# sx-wdec84-1_1.net
KiCad netlist of a schematic drawn in EAGLE
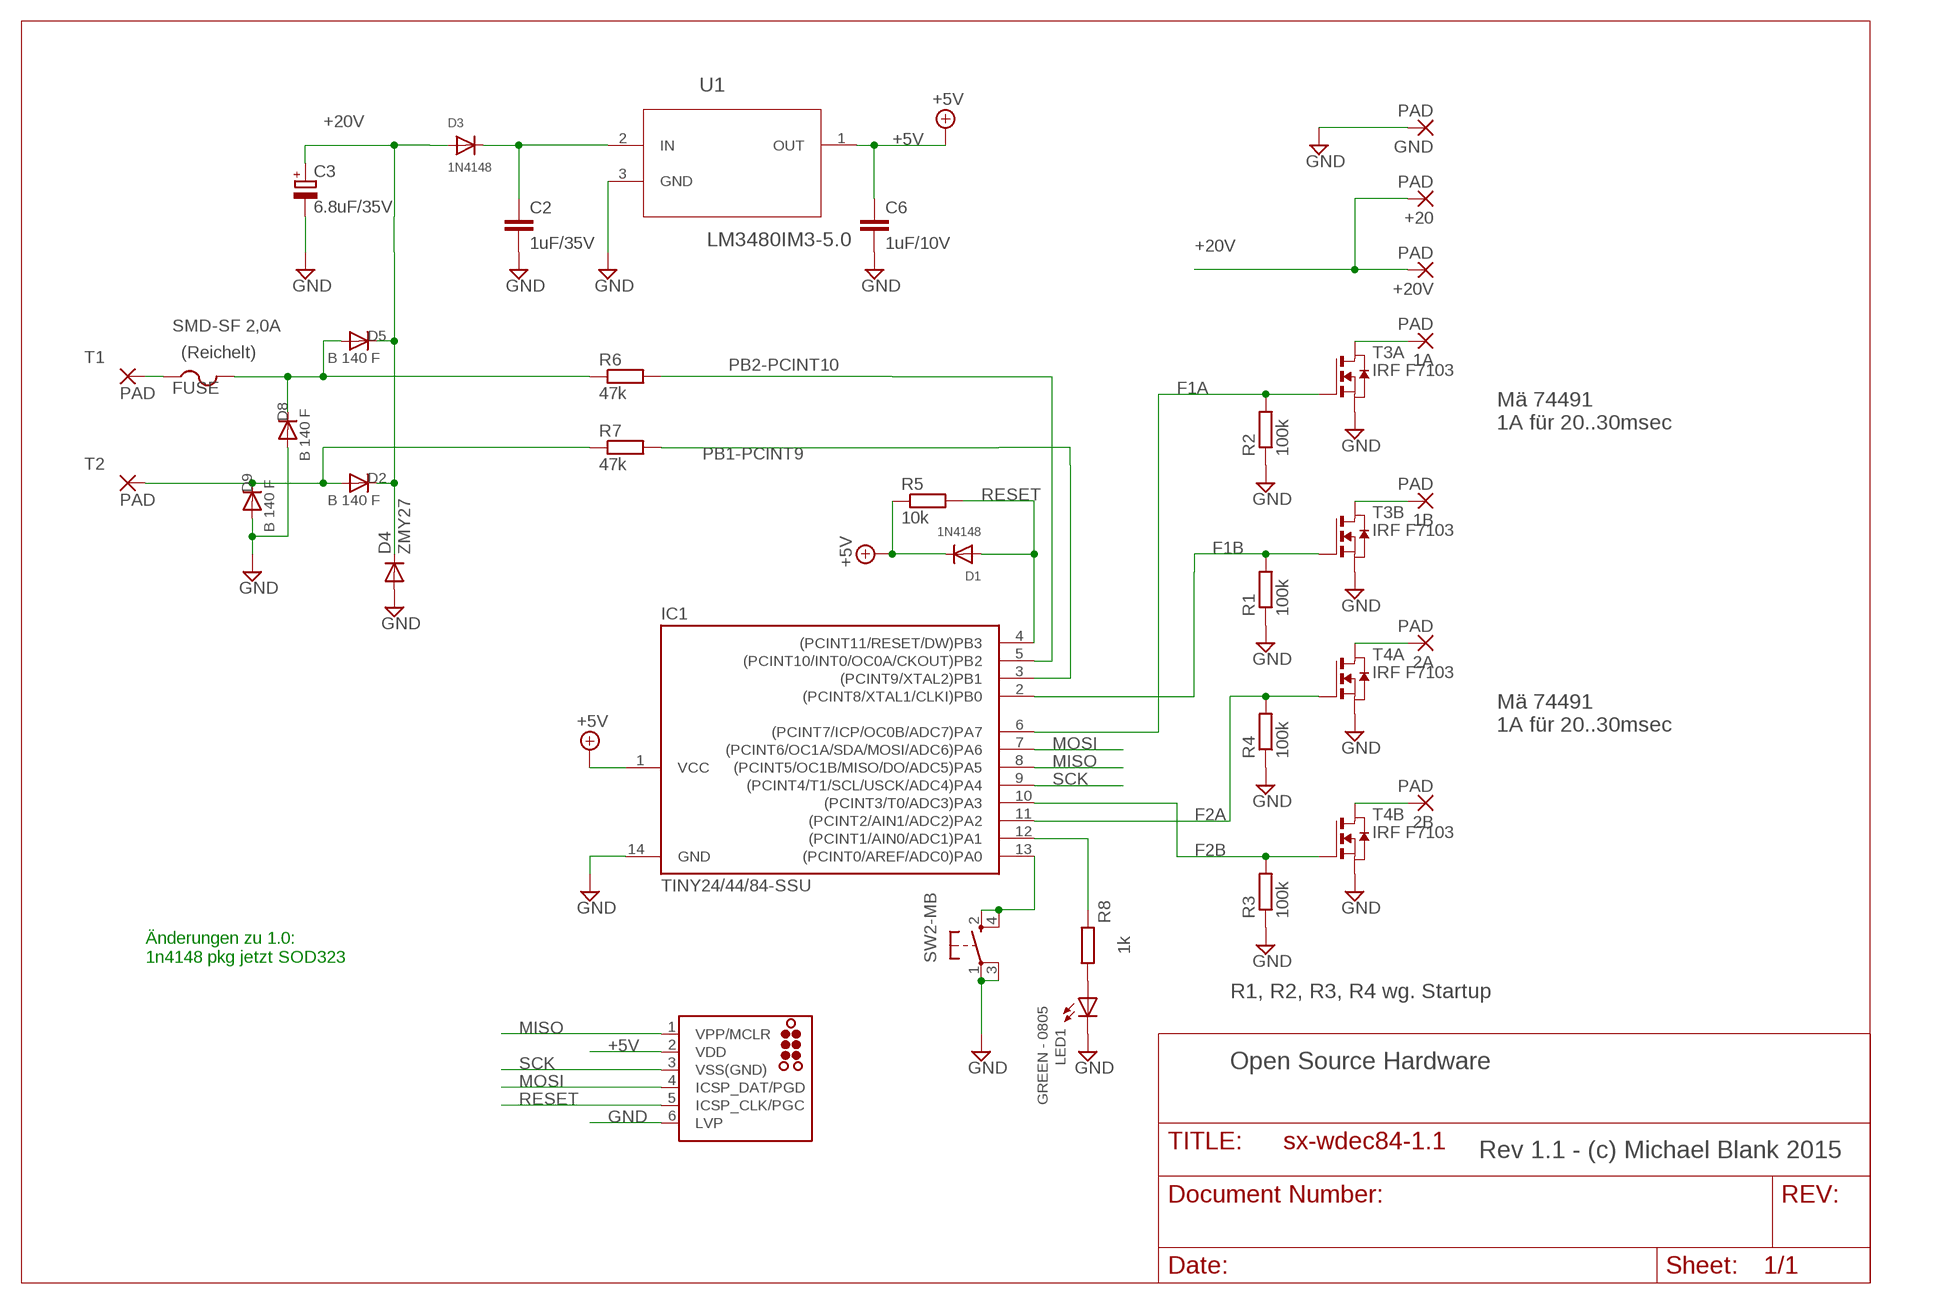
[diagram p0: schematic, sheet 1]

(export (version "E")
  (design (tool "Eeschema 10.0.6"))
  (components
    (comp (ref "+20")
      (value "PAD")
      (footprint "eagle-import:SMD1,27-2,54")
      (libsource (lib "eagle-import") (part "SMD2"))
    )
    (comp (ref "+20V")
      (value "PAD")
      (footprint "eagle-import:SMD1,27-2,54")
      (libsource (lib "eagle-import") (part "SMD2"))
    )
    (comp (ref "1A")
      (value "PAD")
      (footprint "eagle-import:SMD1,27-2,54")
      (libsource (lib "eagle-import") (part "SMD2"))
    )
    (comp (ref "1B")
      (value "PAD")
      (footprint "eagle-import:SMD1,27-2,54")
      (libsource (lib "eagle-import") (part "SMD2"))
    )
    (comp (ref "2A")
      (value "PAD")
      (footprint "eagle-import:SMD1,27-2,54")
      (libsource (lib "eagle-import") (part "SMD2"))
    )
    (comp (ref "2B")
      (value "PAD")
      (footprint "eagle-import:SMD1,27-2,54")
      (libsource (lib "eagle-import") (part "SMD2"))
    )
    (comp (ref "C2")
      (value "1uF/35V")
      (footprint "eagle-import:C0805")
      (libsource (lib "eagle-import") (part "C-EUC0805"))
    )
    (comp (ref "C3")
      (value "6.8uF/35V")
      (footprint "eagle-import:SMC_D")
      (libsource (lib "eagle-import") (part "CPOL-EUSMCD"))
    )
    (comp (ref "C6")
      (value "1uF/10V")
      (footprint "eagle-import:C0805")
      (libsource (lib "eagle-import") (part "C-EUC0805"))
    )
    (comp (ref "D1")
      (value "1N4148")
      (footprint "eagle-import:SOD-323F")
      (libsource (lib "eagle-import") (part "DIODESOD-323F"))
    )
    (comp (ref "D2")
      (value "B 140 F")
      (footprint "eagle-import:SMA-403D")
      (libsource (lib "eagle-import") (part "DIODESMA-403D"))
    )
    (comp (ref "D3")
      (value "1N4148")
      (footprint "eagle-import:SOD-323F")
      (libsource (lib "eagle-import") (part "DIODESOD-323F"))
    )
    (comp (ref "D4")
      (value "ZMY27")
      (footprint "eagle-import:MELF-MLL41")
      (libsource (lib "eagle-import") (part "DIODE-MELF-MLL41"))
    )
    (comp (ref "D5")
      (value "B 140 F")
      (footprint "eagle-import:SMA-403D")
      (libsource (lib "eagle-import") (part "DIODESMA-403D"))
    )
    (comp (ref "D8")
      (value "B 140 F")
      (footprint "eagle-import:SMA-403D")
      (libsource (lib "eagle-import") (part "DIODESMA-403D"))
    )
    (comp (ref "D9")
      (value "B 140 F")
      (footprint "eagle-import:SMA-403D")
      (libsource (lib "eagle-import") (part "DIODESMA-403D"))
    )
    (comp (ref "FUSE")
      (value "SMD-SF 2,0A")
      (footprint "eagle-import:1812")
      (libsource (lib "eagle-import") (part "PTCFUSE-1812"))
    )
    (comp (ref "GND")
      (value "PAD")
      (footprint "eagle-import:SMD1,27-2,54")
      (libsource (lib "eagle-import") (part "SMD2"))
    )
    (comp (ref "IC1")
      (value "TINY24/44/84-SSU")
      (footprint "eagle-import:SOIC14")
      (libsource (lib "eagle-import") (part "TINY24/44/84-SSU"))
    )
    (comp (ref "J1")
      (value "ISP")
      (footprint "eagle-import:TC2030-MCP-NL")
      (libsource (lib "eagle-import") (part "TC2030-MCP-NL"))
    )
    (comp (ref "LED1")
      (value "GREEN - 0805")
      (footprint "eagle-import:LED-0805")
      (libsource (lib "eagle-import") (part "LED0805"))
    )
    (comp (ref "R1")
      (value "100k")
      (footprint "eagle-import:R0805W")
      (libsource (lib "eagle-import") (part "R-EU_R0805W"))
    )
    (comp (ref "R2")
      (value "100k")
      (footprint "eagle-import:R0805W")
      (libsource (lib "eagle-import") (part "R-EU_R0805W"))
    )
    (comp (ref "R3")
      (value "100k")
      (footprint "eagle-import:R0805W")
      (libsource (lib "eagle-import") (part "R-EU_R0805W"))
    )
    (comp (ref "R4")
      (value "100k")
      (footprint "eagle-import:R0805W")
      (libsource (lib "eagle-import") (part "R-EU_R0805W"))
    )
    (comp (ref "R5")
      (value "10k")
      (footprint "eagle-import:R0805W")
      (libsource (lib "eagle-import") (part "R-EU_R0805W"))
    )
    (comp (ref "R6")
      (value "47k")
      (footprint "eagle-import:R0805W")
      (libsource (lib "eagle-import") (part "R-EU_R0805W"))
    )
    (comp (ref "R7")
      (value "47k")
      (footprint "eagle-import:R0805W")
      (libsource (lib "eagle-import") (part "R-EU_R0805W"))
    )
    (comp (ref "R8")
      (value "1k")
      (footprint "eagle-import:R0805W")
      (libsource (lib "eagle-import") (part "R-EU_R0805W"))
    )
    (comp (ref "SW2-MB")
      (value "SPST_TACT-KMR2")
      (footprint "eagle-import:KMR2")
      (libsource (lib "eagle-import") (part "SPST_TACT-KMR2"))
    )
    (comp (ref "T1")
      (value "PAD")
      (footprint "eagle-import:SMD1,27-2,54")
      (libsource (lib "eagle-import") (part "SMD2"))
    )
    (comp (ref "T2")
      (value "PAD")
      (footprint "eagle-import:SMD1,27-2,54")
      (libsource (lib "eagle-import") (part "SMD2"))
    )
    (comp (ref "T3")
      (value "IRF F7103")
      (footprint "eagle-import:SO8")
      (libsource (lib "eagle-import") (part "DMN3024LSD"))
    )
    (comp (ref "T4")
      (value "IRF F7103")
      (footprint "eagle-import:SO8")
      (libsource (lib "eagle-import") (part "DMN3024LSD"))
    )
    (comp (ref "U1")
      (value "LM3480IM3-5.0")
      (footprint "eagle-import:SOT95P263X110-3N")
      (fields (field (name "MPN") "LM3480IM3-50"))
      (libsource (lib "eagle-import") (part "LM3480IM3-5.0"))
    )
  )
  (nets
    (net (code "1") (name "+5V") (class "Default")
      (node (ref "C6") (pin "1") (pinfunction "1_1") (pintype "passive"))
      (node (ref "D1") (pin "C") (pinfunction "C_C") (pintype "passive"))
      (node (ref "IC1") (pin "1") (pinfunction "VCC_1") (pintype "power_in"))
      (node (ref "J1") (pin "2") (pinfunction "VDD_2") (pintype "power_in"))
      (node (ref "R5") (pin "1") (pinfunction "1_1") (pintype "passive"))
      (node (ref "U1") (pin "1") (pinfunction "OUT_1") (pintype "output"))
    )
    (net (code "2") (name "/+20V") (class "Default")
      (node (ref "+20") (pin "1") (pinfunction "P_1") (pintype "passive"))
      (node (ref "+20V") (pin "1") (pinfunction "P_1") (pintype "passive"))
      (node (ref "C3") (pin "+") (pinfunction "+_+") (pintype "passive"))
      (node (ref "D2") (pin "C") (pinfunction "C_C") (pintype "passive"))
      (node (ref "D3") (pin "A") (pinfunction "A_A") (pintype "passive"))
      (node (ref "D4") (pin "C") (pinfunction "C_C") (pintype "passive"))
      (node (ref "D5") (pin "C") (pinfunction "C_C") (pintype "passive"))
    )
    (net (code "3") (name "/F1A") (class "Default")
      (node (ref "IC1") (pin "6") (pinfunction "(PCINT7/ICP/OC0B/ADC7)PA7_6") (pintype "bidirectional"))
      (node (ref "R2") (pin "2") (pinfunction "2_2") (pintype "passive"))
      (node (ref "T3") (pin "2") (pinfunction "G_2") (pintype "passive"))
    )
    (net (code "4") (name "/F1B") (class "Default")
      (node (ref "IC1") (pin "2") (pinfunction "(PCINT8/XTAL1/CLKI)PB0_2") (pintype "bidirectional"))
      (node (ref "R1") (pin "2") (pinfunction "2_2") (pintype "passive"))
      (node (ref "T3") (pin "4") (pinfunction "G_4") (pintype "passive"))
    )
    (net (code "5") (name "/F2A") (class "Default")
      (node (ref "IC1") (pin "11") (pinfunction "(PCINT2/AIN1/ADC2)PA2_11") (pintype "bidirectional"))
      (node (ref "R4") (pin "2") (pinfunction "2_2") (pintype "passive"))
      (node (ref "T4") (pin "2") (pinfunction "G_2") (pintype "passive"))
    )
    (net (code "6") (name "/F2B") (class "Default")
      (node (ref "IC1") (pin "10") (pinfunction "(PCINT3/T0/ADC3)PA3_10") (pintype "bidirectional"))
      (node (ref "R3") (pin "2") (pinfunction "2_2") (pintype "passive"))
      (node (ref "T4") (pin "4") (pinfunction "G_4") (pintype "passive"))
    )
    (net (code "7") (name "/MISO") (class "Default")
      (node (ref "IC1") (pin "8") (pinfunction "(PCINT5/OC1B/MISO/DO/ADC5)PA5_8") (pintype "bidirectional"))
      (node (ref "J1") (pin "1") (pinfunction "VPP/MCLR_1") (pintype "passive"))
    )
    (net (code "8") (name "/MOSI") (class "Default")
      (node (ref "IC1") (pin "7") (pinfunction "(PCINT6/OC1A/SDA/MOSI/ADC6)PA6_7") (pintype "bidirectional"))
      (node (ref "J1") (pin "4") (pinfunction "ICSP_DAT/PGD_4") (pintype "bidirectional"))
    )
    (net (code "9") (name "/PB1-PCINT9") (class "Default")
      (node (ref "IC1") (pin "3") (pinfunction "(PCINT9/XTAL2)PB1_3") (pintype "bidirectional"))
      (node (ref "R7") (pin "2") (pinfunction "2_2") (pintype "passive"))
    )
    (net (code "10") (name "/PB2-PCINT10") (class "Default")
      (node (ref "IC1") (pin "5") (pinfunction "(PCINT10/INT0/OC0A/CKOUT)PB2_5") (pintype "bidirectional"))
      (node (ref "R6") (pin "2") (pinfunction "2_2") (pintype "passive"))
    )
    (net (code "11") (name "/RESET") (class "Default")
      (node (ref "D1") (pin "A") (pinfunction "A_A") (pintype "passive"))
      (node (ref "IC1") (pin "4") (pinfunction "(PCINT11/RESET/DW)PB3_4") (pintype "bidirectional"))
      (node (ref "J1") (pin "5") (pinfunction "ICSP_CLK/PGC_5") (pintype "output"))
      (node (ref "R5") (pin "2") (pinfunction "2_2") (pintype "passive"))
    )
    (net (code "12") (name "/SCK") (class "Default")
      (node (ref "IC1") (pin "9") (pinfunction "(PCINT4/T1/SCL/USCK/ADC4)PA4_9") (pintype "bidirectional"))
      (node (ref "J1") (pin "3") (pinfunction "VSS(GND)_3") (pintype "power_in"))
    )
    (net (code "13") (name "GND") (class "Default")
      (node (ref "C2") (pin "2") (pinfunction "2_2") (pintype "passive"))
      (node (ref "C3") (pin "-") (pinfunction "-_-") (pintype "passive"))
      (node (ref "C6") (pin "2") (pinfunction "2_2") (pintype "passive"))
      (node (ref "D4") (pin "A") (pinfunction "A_A") (pintype "passive"))
      (node (ref "D8") (pin "A") (pinfunction "A_A") (pintype "passive"))
      (node (ref "D9") (pin "A") (pinfunction "A_A") (pintype "passive"))
      (node (ref "GND") (pin "1") (pinfunction "P_1") (pintype "passive"))
      (node (ref "IC1") (pin "14") (pinfunction "GND_14") (pintype "power_in"))
      (node (ref "J1") (pin "6") (pinfunction "LVP_6") (pintype "bidirectional"))
      (node (ref "LED1") (pin "C") (pinfunction "C_C") (pintype "passive"))
      (node (ref "R1") (pin "1") (pinfunction "1_1") (pintype "passive"))
      (node (ref "R2") (pin "1") (pinfunction "1_1") (pintype "passive"))
      (node (ref "R3") (pin "1") (pinfunction "1_1") (pintype "passive"))
      (node (ref "R4") (pin "1") (pinfunction "1_1") (pintype "passive"))
      (node (ref "SW2-MB") (pin "1") (pinfunction "P_1") (pintype "passive"))
      (node (ref "SW2-MB") (pin "3") (pinfunction "P1_3") (pintype "passive"))
      (node (ref "T3") (pin "1") (pinfunction "S_1") (pintype "passive"))
      (node (ref "T3") (pin "3") (pinfunction "S_3") (pintype "passive"))
      (node (ref "T4") (pin "1") (pinfunction "S_1") (pintype "passive"))
      (node (ref "T4") (pin "3") (pinfunction "S_3") (pintype "passive"))
      (node (ref "U1") (pin "3") (pinfunction "GND_3") (pintype "passive"))
    )
    (net (code "14") (name "Net-(1A-P)") (class "Default")
      (node (ref "1A") (pin "1") (pinfunction "P_1") (pintype "passive"))
      (node (ref "T3") (pin "7") (pinfunction "D_7") (pintype "passive"))
      (node (ref "T3") (pin "8") (pinfunction "D_8") (pintype "passive"))
    )
    (net (code "15") (name "Net-(1B-P)") (class "Default")
      (node (ref "1B") (pin "1") (pinfunction "P_1") (pintype "passive"))
      (node (ref "T3") (pin "5") (pinfunction "D_5") (pintype "passive"))
      (node (ref "T3") (pin "6") (pinfunction "D_6") (pintype "passive"))
    )
    (net (code "16") (name "Net-(2A-P)") (class "Default")
      (node (ref "2A") (pin "1") (pinfunction "P_1") (pintype "passive"))
      (node (ref "T4") (pin "7") (pinfunction "D_7") (pintype "passive"))
      (node (ref "T4") (pin "8") (pinfunction "D_8") (pintype "passive"))
    )
    (net (code "17") (name "Net-(2B-P)") (class "Default")
      (node (ref "2B") (pin "1") (pinfunction "P_1") (pintype "passive"))
      (node (ref "T4") (pin "5") (pinfunction "D_5") (pintype "passive"))
      (node (ref "T4") (pin "6") (pinfunction "D_6") (pintype "passive"))
    )
    (net (code "18") (name "Net-(D5-PadA)") (class "Default")
      (node (ref "D5") (pin "A") (pinfunction "A_A") (pintype "passive"))
      (node (ref "D8") (pin "C") (pinfunction "C_C") (pintype "passive"))
      (node (ref "FUSE") (pin "2") (pinfunction "2_2") (pintype "passive"))
      (node (ref "R6") (pin "1") (pinfunction "1_1") (pintype "passive"))
    )
    (net (code "19") (name "Net-(IC1-(PCINT0{slash}AREF{slash}ADC0)PA0)") (class "Default")
      (node (ref "IC1") (pin "13") (pinfunction "(PCINT0/AREF/ADC0)PA0_13") (pintype "bidirectional"))
      (node (ref "SW2-MB") (pin "2") (pinfunction "S_2") (pintype "passive"))
      (node (ref "SW2-MB") (pin "4") (pinfunction "S1_4") (pintype "passive"))
    )
    (net (code "20") (name "Net-(IC1-(PCINT1{slash}AIN0{slash}ADC1)PA1)") (class "Default")
      (node (ref "IC1") (pin "12") (pinfunction "(PCINT1/AIN0/ADC1)PA1_12") (pintype "bidirectional"))
      (node (ref "R8") (pin "1") (pinfunction "1_1") (pintype "passive"))
    )
    (net (code "21") (name "Net-(LED1-PadA)") (class "Default")
      (node (ref "LED1") (pin "A") (pinfunction "A_A") (pintype "passive"))
      (node (ref "R8") (pin "2") (pinfunction "2_2") (pintype "passive"))
    )
    (net (code "22") (name "Net-(T1-P)") (class "Default")
      (node (ref "FUSE") (pin "1") (pinfunction "1_1") (pintype "passive"))
      (node (ref "T1") (pin "1") (pinfunction "P_1") (pintype "passive"))
    )
    (net (code "23") (name "Net-(T2-P)") (class "Default")
      (node (ref "D2") (pin "A") (pinfunction "A_A") (pintype "passive"))
      (node (ref "D9") (pin "C") (pinfunction "C_C") (pintype "passive"))
      (node (ref "R7") (pin "1") (pinfunction "1_1") (pintype "passive"))
      (node (ref "T2") (pin "1") (pinfunction "P_1") (pintype "passive"))
    )
    (net (code "24") (name "Net-(U1-IN)") (class "Default")
      (node (ref "C2") (pin "1") (pinfunction "1_1") (pintype "passive"))
      (node (ref "D3") (pin "C") (pinfunction "C_C") (pintype "passive"))
      (node (ref "U1") (pin "2") (pinfunction "IN_2") (pintype "power_in"))
    )
  )
)
